# Sheet5.net
KiCad netlist of a schematic drawn in Altium Designer
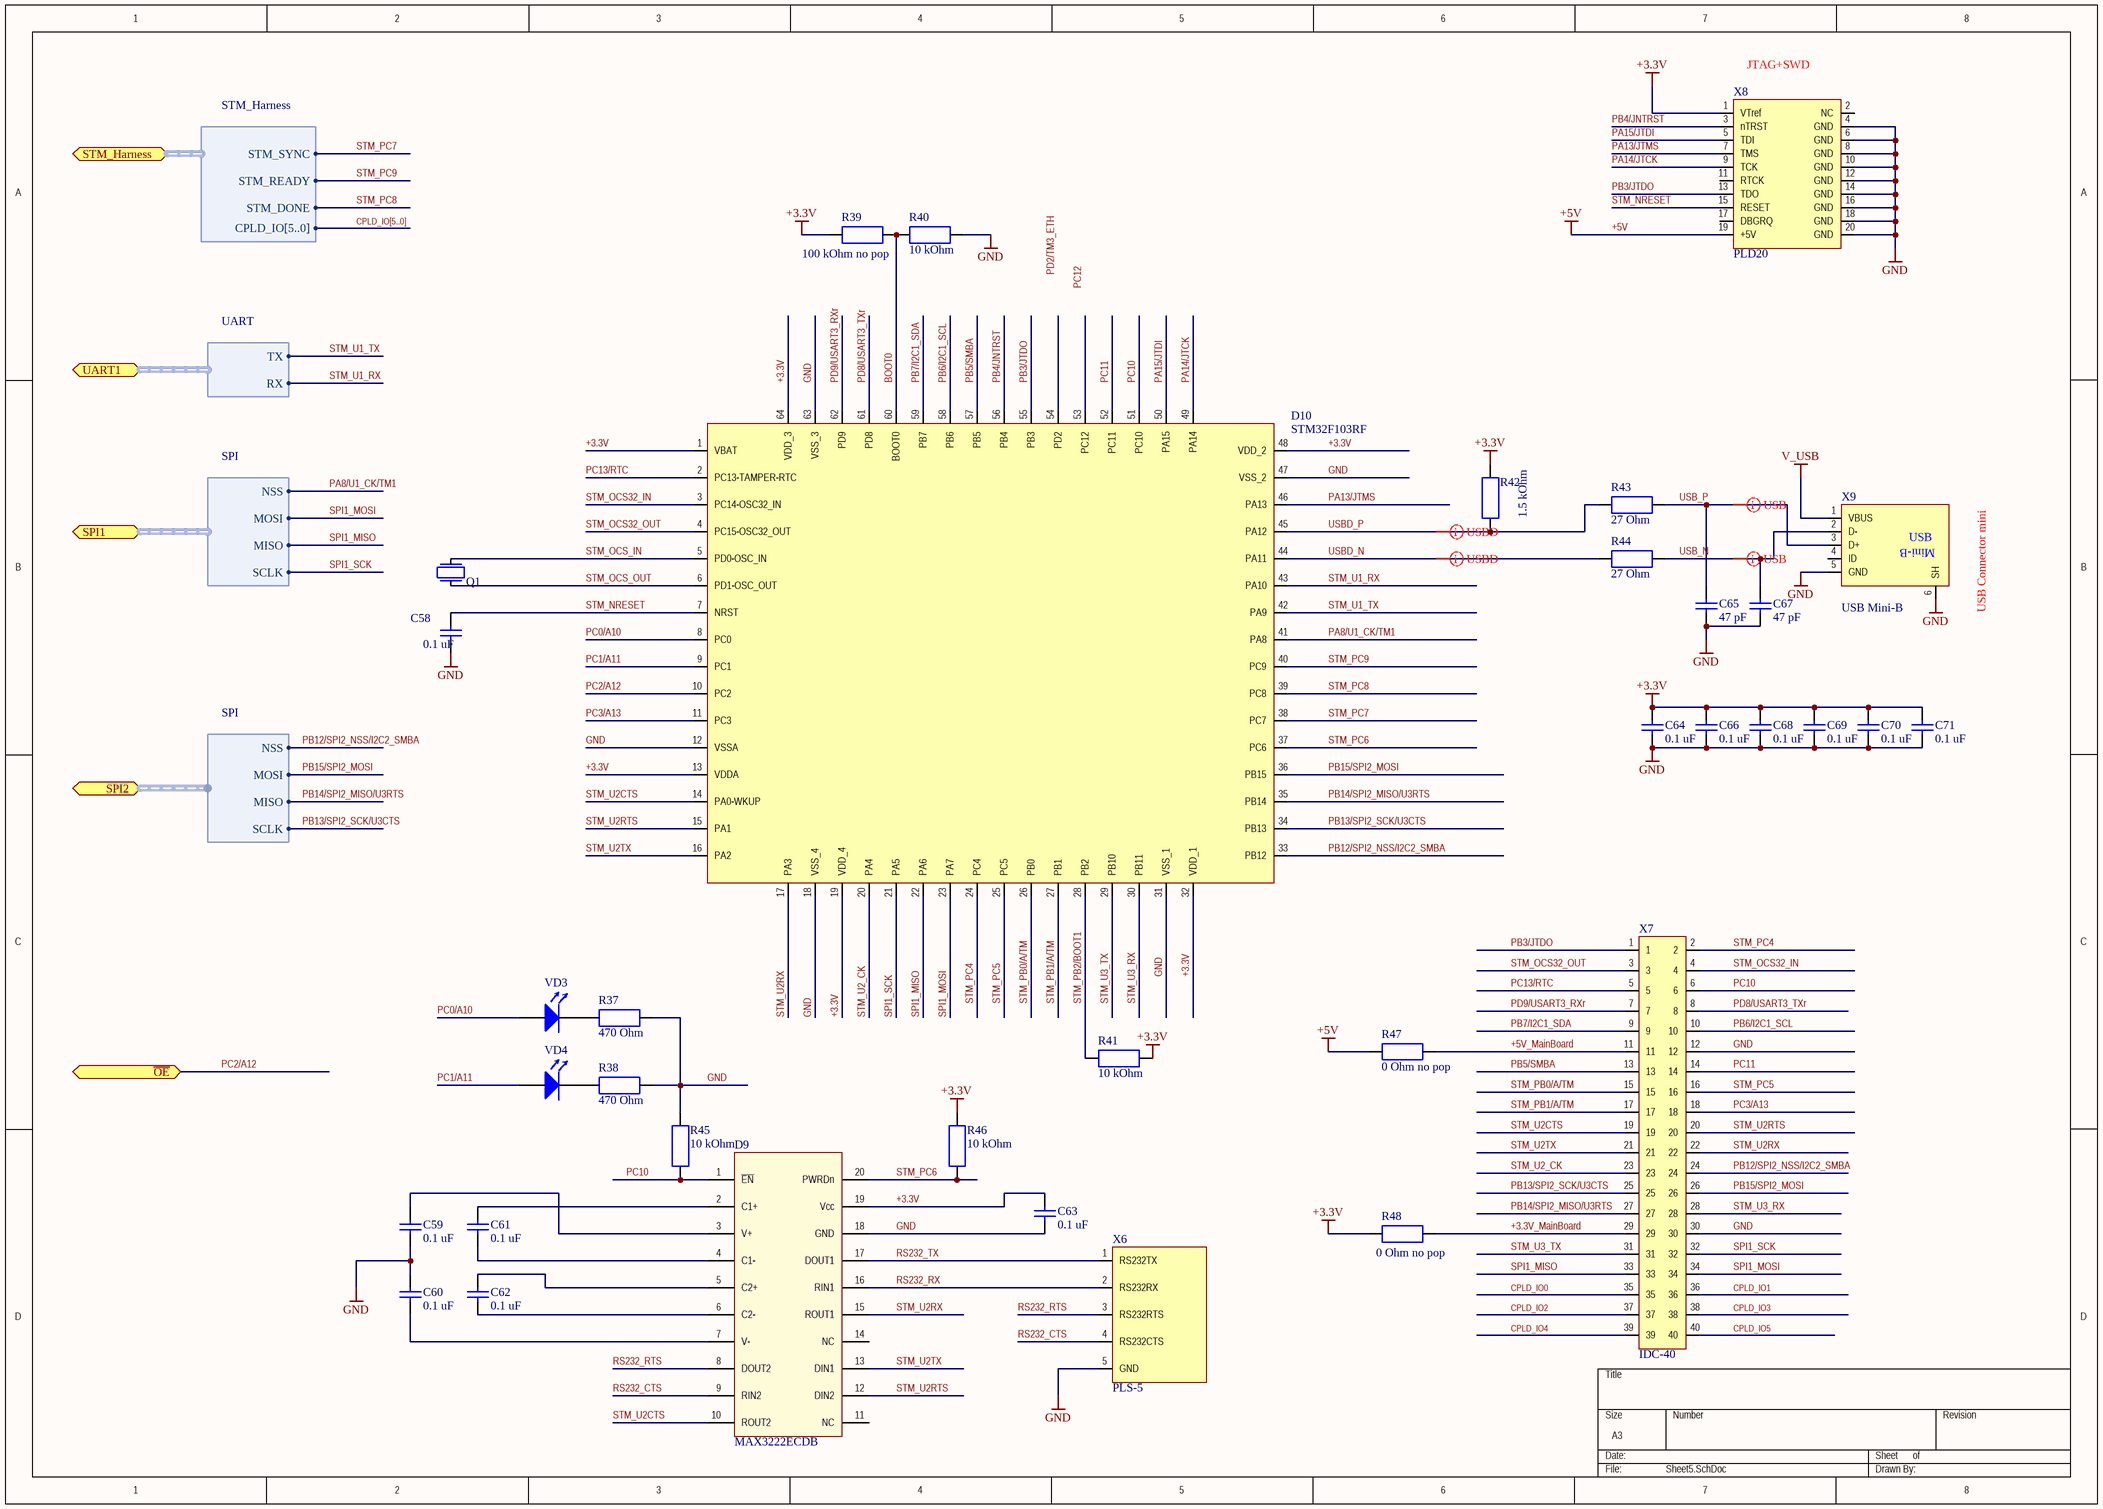
[diagram p0: Sheet5.SchDoc]

(export (version "E")
  (design (tool "Eeschema 10.0.6"))
  (components
    (comp (ref "C58")
      (value "0.1 uF")
      (footprint "CAPC1608N")
      (description "±10%, X7R, 0603")
      (fields (field (name "PUBLISHER") "DS"))
      (libsource (lib "autotracker") (part "CC0603"))
    )
    (comp (ref "C59")
      (value "0.1 uF")
      (footprint "CAPC1608N")
      (description "±10%, X7R, 0603")
      (fields (field (name "PUBLISHER") "DS"))
      (libsource (lib "ADClib") (part "CC0603"))
    )
    (comp (ref "C60")
      (value "0.1 uF")
      (footprint "CAPC1608N")
      (description "±10%, X7R, 0603")
      (fields (field (name "PUBLISHER") "DS"))
      (libsource (lib "ADClib") (part "CC0603"))
    )
    (comp (ref "C61")
      (value "0.1 uF")
      (footprint "CAPC1608N")
      (description "±10%, X7R, 0603")
      (fields (field (name "PUBLISHER") "DS"))
      (libsource (lib "ADClib") (part "CC0603"))
    )
    (comp (ref "C62")
      (value "0.1 uF")
      (footprint "CAPC1608N")
      (description "±10%, X7R, 0603")
      (fields (field (name "PUBLISHER") "DS"))
      (libsource (lib "ADClib") (part "CC0603"))
    )
    (comp (ref "C63")
      (value "0.1 uF")
      (footprint "CAPC1608N")
      (description "±10%, X7R, 0603")
      (fields (field (name "PUBLISHER") "DS"))
      (libsource (lib "ADClib") (part "CC0603"))
    )
    (comp (ref "C64")
      (value "0.1 uF")
      (footprint "CAPC1608N")
      (description "±10%, X7R, 0603")
      (fields (field (name "PUBLISHER") "DS"))
      (libsource (lib "autotracker") (part "CC0603"))
    )
    (comp (ref "C65")
      (value "47 pF")
      (footprint "CAPC1608N")
      (description "±10%, X7R, 0603")
      (fields (field (name "PUBLISHER") "DS"))
      (libsource (lib "autotracker") (part "CC0603"))
    )
    (comp (ref "C66")
      (value "0.1 uF")
      (footprint "CAPC1608N")
      (description "±10%, X7R, 0603")
      (fields (field (name "PUBLISHER") "DS"))
      (libsource (lib "autotracker") (part "CC0603"))
    )
    (comp (ref "C67")
      (value "47 pF")
      (footprint "CAPC1608N")
      (description "±10%, X7R, 0603")
      (fields (field (name "PUBLISHER") "DS"))
      (libsource (lib "autotracker") (part "CC0603"))
    )
    (comp (ref "C68")
      (value "0.1 uF")
      (footprint "CAPC1608N")
      (description "±10%, X7R, 0603")
      (fields (field (name "PUBLISHER") "DS"))
      (libsource (lib "autotracker") (part "CC0603"))
    )
    (comp (ref "C69")
      (value "0.1 uF")
      (footprint "CAPC1608N")
      (description "±10%, X7R, 0603")
      (fields (field (name "PUBLISHER") "DS"))
      (libsource (lib "autotracker") (part "CC0603"))
    )
    (comp (ref "C70")
      (value "0.1 uF")
      (footprint "CAPC1608N")
      (description "±10%, X7R, 0603")
      (fields (field (name "PUBLISHER") "DS"))
      (libsource (lib "autotracker") (part "CC0603"))
    )
    (comp (ref "C71")
      (value "0.1 uF")
      (footprint "CAPC1608N")
      (description "±10%, X7R, 0603")
      (fields (field (name "PUBLISHER") "DS"))
      (libsource (lib "autotracker") (part "CC0603"))
    )
    (comp (ref "D9")
      (value "MAX3222ECDB")
      (footprint "SOP65P780X200-20N")
      (description "RS232 driver")
      (libsource (lib "ADClib") (part "MAX3222ECDB"))
    )
    (comp (ref "D10")
      (value "STM32F103RF")
      (footprint "LQFP64")
      (description "STM32F103RF LQFP64")
      (libsource (lib "ADClib") (part "STM32F103RF"))
    )
    (comp (ref "Q1")
      (value "Quarz")
      (footprint "HC-49/U3H")
      (description "Ceramic quarz")
      (fields (field (name "PUBLISHER") "DS"))
      (libsource (lib "ADClib") (part "Quarz"))
    )
    (comp (ref "R37")
      (value "470 Ohm")
      (footprint "RESC1608N")
      (description "±5%, 0603")
      (fields (field (name "PUBLISHER") "DS"))
      (libsource (lib "ADClib") (part "RES0603"))
    )
    (comp (ref "R38")
      (value "470 Ohm")
      (footprint "RESC1608N")
      (description "±5%, 0603")
      (fields (field (name "PUBLISHER") "DS"))
      (libsource (lib "ADClib") (part "RES0603"))
    )
    (comp (ref "R39")
      (value "100 kOhm no pop")
      (footprint "RESC1608N")
      (description "±5%, 0603")
      (fields (field (name "PUBLISHER") "DS"))
      (libsource (lib "autotracker") (part "RES0603"))
    )
    (comp (ref "R40")
      (value "10 kOhm")
      (footprint "RESC1608N")
      (description "±5%, 0603")
      (fields (field (name "PUBLISHER") "DS"))
      (libsource (lib "autotracker") (part "RES0603"))
    )
    (comp (ref "R41")
      (value "10 kOhm")
      (footprint "RESC1608N")
      (description "±5%, 0603")
      (fields (field (name "PUBLISHER") "DS"))
      (libsource (lib "autotracker") (part "RES0603"))
    )
    (comp (ref "R42")
      (value "1.5 kOhm")
      (footprint "RESC1608N")
      (description "±5%, 0603")
      (fields (field (name "PUBLISHER") "DS"))
      (libsource (lib "autotracker") (part "RES0603"))
    )
    (comp (ref "R43")
      (value "27 Ohm")
      (footprint "RESC1608N")
      (description "±5%, 0603")
      (fields (field (name "PUBLISHER") "DS"))
      (libsource (lib "autotracker") (part "RES0603"))
    )
    (comp (ref "R44")
      (value "27 Ohm")
      (footprint "RESC1608N")
      (description "±5%, 0603")
      (fields (field (name "PUBLISHER") "DS"))
      (libsource (lib "autotracker") (part "RES0603"))
    )
    (comp (ref "R45")
      (value "10 kOhm")
      (footprint "RESC1608N")
      (description "±5%, 0603")
      (fields (field (name "PUBLISHER") "DS"))
      (libsource (lib "ADClib") (part "RES0603"))
    )
    (comp (ref "R46")
      (value "10 kOhm")
      (footprint "RESC1608N")
      (description "±5%, 0603")
      (fields (field (name "PUBLISHER") "DS"))
      (libsource (lib "ADClib") (part "RES0603"))
    )
    (comp (ref "R47")
      (value "0 Ohm no pop")
      (footprint "RESC1608N")
      (description "±5%, 0603")
      (fields (field (name "PUBLISHER") "DS"))
      (libsource (lib "ADClib") (part "RES0603"))
    )
    (comp (ref "R48")
      (value "0 Ohm no pop")
      (footprint "RESC1608N")
      (description "±5%, 0603")
      (fields (field (name "PUBLISHER") "DS"))
      (libsource (lib "ADClib") (part "RES0603"))
    )
    (comp (ref "VD3")
      (value "KP-1608SURC")
      (footprint "LED1608N")
      (fields (field (name "PUBLISHER") "Altium Limited"))
      (libsource (lib "ADClib") (part "KP-1608SURC"))
    )
    (comp (ref "VD4")
      (value "KP-1608SURC")
      (footprint "LED1608N")
      (fields (field (name "PUBLISHER") "Altium Limited"))
      (libsource (lib "ADClib") (part "KP-1608SURC"))
    )
    (comp (ref "X6") (value "PLS-5") (footprint "PLS-5") (libsource (lib "ADClib") (part "RS232")))
    (comp (ref "X7")
      (value "IDC-40")
      (footprint "PLD-40")
      (description "PLD-40 or IDC 40")
      (libsource (lib "ADClib") (part "IDC40"))
    )
    (comp (ref "X8") (value "PLD20") (footprint "PLD-20") (libsource (lib "autotracker") (part "JTAG")))
    (comp (ref "X9")
      (value "USB Mini-B")
      (footprint "USBMINIB")
      (libsource (lib "autotracker") (part "USB-MINI-B"))
    )
  )
  (nets
    (net (code "4") (name "+3.3V") (class "Default")
      (node (ref "C63") (pin "2") (pinfunction "2_2") (pintype "passive"))
      (node (ref "C64") (pin "2") (pinfunction "2_2") (pintype "passive"))
      (node (ref "C66") (pin "2") (pinfunction "2_2") (pintype "passive"))
      (node (ref "C68") (pin "2") (pinfunction "2_2") (pintype "passive"))
      (node (ref "C69") (pin "2") (pinfunction "2_2") (pintype "passive"))
      (node (ref "C70") (pin "2") (pinfunction "2_2") (pintype "passive"))
      (node (ref "C71") (pin "2") (pinfunction "2_2") (pintype "passive"))
      (node (ref "D10") (pin "1") (pinfunction "VBAT_1") (pintype "passive"))
      (node (ref "D10") (pin "13") (pinfunction "VDDA_13") (pintype "passive"))
      (node (ref "D10") (pin "19") (pinfunction "VDD_4_19") (pintype "passive"))
      (node (ref "D10") (pin "32") (pinfunction "VDD_1_32") (pintype "passive"))
      (node (ref "D10") (pin "48") (pinfunction "VDD_2_48") (pintype "passive"))
      (node (ref "D10") (pin "64") (pinfunction "VDD_3_64") (pintype "passive"))
      (node (ref "D9") (pin "19") (pinfunction "Vcc_19") (pintype "passive"))
      (node (ref "R39") (pin "2") (pinfunction "2_2") (pintype "passive"))
      (node (ref "R41") (pin "1") (pinfunction "1_1") (pintype "passive"))
      (node (ref "R42") (pin "2") (pinfunction "2_2") (pintype "passive"))
      (node (ref "R46") (pin "2") (pinfunction "2_2") (pintype "passive"))
      (node (ref "R48") (pin "2") (pinfunction "2_2") (pintype "passive"))
      (node (ref "X8") (pin "1") (pinfunction "VTref_1") (pintype "passive"))
    )
    (net (code "5") (name "+5V") (class "Default")
      (node (ref "R47") (pin "2") (pinfunction "2_2") (pintype "passive"))
      (node (ref "X8") (pin "19") (pinfunction "+5V_19") (pintype "passive"))
    )
    (net (code "6") (name "/+3.3V_MainBoard") (class "Default")
      (node (ref "R48") (pin "1") (pinfunction "1_1") (pintype "passive"))
      (node (ref "X7") (pin "29") (pinfunction "29_29") (pintype "passive"))
    )
    (net (code "7") (name "/+5V_MainBoard") (class "Default")
      (node (ref "R47") (pin "1") (pinfunction "1_1") (pintype "passive"))
      (node (ref "X7") (pin "11") (pinfunction "11_11") (pintype "passive"))
    )
    (net (code "8") (name "/BOOT0") (class "Default")
      (node (ref "D10") (pin "60") (pinfunction "BOOT0_60") (pintype "passive"))
      (node (ref "R39") (pin "1") (pinfunction "1_1") (pintype "passive"))
      (node (ref "R40") (pin "2") (pinfunction "2_2") (pintype "passive"))
    )
    (net (code "9") (name "/CPLD_IO0") (class "Default")
      (node (ref "X7") (pin "35") (pinfunction "35_35") (pintype "passive"))
    )
    (net (code "10") (name "/CPLD_IO1") (class "Default")
      (node (ref "X7") (pin "36") (pinfunction "36_36") (pintype "passive"))
    )
    (net (code "11") (name "/CPLD_IO2") (class "Default")
      (node (ref "X7") (pin "37") (pinfunction "37_37") (pintype "passive"))
    )
    (net (code "12") (name "/CPLD_IO3") (class "Default")
      (node (ref "X7") (pin "38") (pinfunction "38_38") (pintype "passive"))
    )
    (net (code "13") (name "/CPLD_IO4") (class "Default")
      (node (ref "X7") (pin "39") (pinfunction "39_39") (pintype "passive"))
    )
    (net (code "14") (name "/CPLD_IO5") (class "Default")
      (node (ref "X7") (pin "40") (pinfunction "40_40") (pintype "passive"))
    )
    (net (code "15") (name "/PA8{slash}U1_CK{slash}TM1") (class "Default")
      (node (ref "D10") (pin "41") (pinfunction "PA8_41") (pintype "passive"))
    )
    (net (code "16") (name "/PA13{slash}JTMS") (class "Default")
      (node (ref "D10") (pin "46") (pinfunction "PA13_46") (pintype "passive"))
      (node (ref "X8") (pin "7") (pinfunction "TMS_7") (pintype "passive"))
    )
    (net (code "17") (name "/PA14{slash}JTCK") (class "Default")
      (node (ref "D10") (pin "49") (pinfunction "PA14_49") (pintype "passive"))
      (node (ref "X8") (pin "9") (pinfunction "TCK_9") (pintype "passive"))
    )
    (net (code "18") (name "/PA15{slash}JTDI") (class "Default")
      (node (ref "D10") (pin "50") (pinfunction "PA15_50") (pintype "passive"))
      (node (ref "X8") (pin "5") (pinfunction "TDI_5") (pintype "passive"))
    )
    (net (code "19") (name "/PB3{slash}JTDO") (class "Default")
      (node (ref "D10") (pin "55") (pinfunction "PB3_55") (pintype "passive"))
      (node (ref "X7") (pin "1") (pinfunction "1_1") (pintype "passive"))
      (node (ref "X8") (pin "13") (pinfunction "TDO_13") (pintype "passive"))
    )
    (net (code "20") (name "/PB4{slash}JNTRST") (class "Default")
      (node (ref "D10") (pin "56") (pinfunction "PB4_56") (pintype "passive"))
      (node (ref "X8") (pin "3") (pinfunction "nTRST_3") (pintype "passive"))
    )
    (net (code "21") (name "/PB5{slash}SMBA") (class "Default")
      (node (ref "D10") (pin "57") (pinfunction "PB5_57") (pintype "passive"))
      (node (ref "X7") (pin "13") (pinfunction "13_13") (pintype "passive"))
    )
    (net (code "22") (name "/PB6{slash}I2C1_SCL") (class "Default")
      (node (ref "D10") (pin "58") (pinfunction "PB6_58") (pintype "passive"))
      (node (ref "X7") (pin "10") (pinfunction "10_10") (pintype "passive"))
    )
    (net (code "23") (name "/PB7{slash}I2C1_SDA") (class "Default")
      (node (ref "D10") (pin "59") (pinfunction "PB7_59") (pintype "passive"))
      (node (ref "X7") (pin "9") (pinfunction "9_9") (pintype "passive"))
    )
    (net (code "24") (name "/PB12{slash}SPI2_NSS{slash}I2C2_SMBA") (class "Default")
      (node (ref "D10") (pin "33") (pinfunction "PB12_33") (pintype "passive"))
      (node (ref "X7") (pin "24") (pinfunction "24_24") (pintype "passive"))
    )
    (net (code "25") (name "/PB13{slash}SPI2_SCK{slash}U3CTS") (class "Default")
      (node (ref "D10") (pin "34") (pinfunction "PB13_34") (pintype "passive"))
      (node (ref "X7") (pin "25") (pinfunction "25_25") (pintype "passive"))
    )
    (net (code "26") (name "/PB14{slash}SPI2_MISO{slash}U3RTS") (class "Default")
      (node (ref "D10") (pin "35") (pinfunction "PB14_35") (pintype "passive"))
      (node (ref "X7") (pin "27") (pinfunction "27_27") (pintype "passive"))
    )
    (net (code "27") (name "/PB15{slash}SPI2_MOSI") (class "Default")
      (node (ref "D10") (pin "36") (pinfunction "PB15_36") (pintype "passive"))
      (node (ref "X7") (pin "26") (pinfunction "26_26") (pintype "passive"))
    )
    (net (code "28") (name "/PC0{slash}A10") (class "Default")
      (node (ref "D10") (pin "8") (pinfunction "PC0_8") (pintype "passive"))
      (node (ref "VD3") (pin "1") (pinfunction "A_1") (pintype "passive"))
    )
    (net (code "29") (name "/PC1{slash}A11") (class "Default")
      (node (ref "D10") (pin "9") (pinfunction "PC1_9") (pintype "passive"))
      (node (ref "VD4") (pin "1") (pinfunction "A_1") (pintype "passive"))
    )
    (net (code "30") (name "/PC2{slash}A12") (class "Default")
      (node (ref "D10") (pin "10") (pinfunction "PC2_10") (pintype "passive"))
    )
    (net (code "31") (name "/PC3{slash}A13") (class "Default")
      (node (ref "D10") (pin "11") (pinfunction "PC3_11") (pintype "passive"))
      (node (ref "X7") (pin "18") (pinfunction "18_18") (pintype "passive"))
    )
    (net (code "32") (name "/PC10") (class "Default")
      (node (ref "D10") (pin "51") (pinfunction "PC10_51") (pintype "passive"))
      (node (ref "D9") (pin "1") (pinfunction "~{EN}_1") (pintype "passive"))
      (node (ref "R45") (pin "1") (pinfunction "1_1") (pintype "passive"))
      (node (ref "X7") (pin "6") (pinfunction "6_6") (pintype "passive"))
    )
    (net (code "33") (name "/PC11") (class "Default")
      (node (ref "D10") (pin "52") (pinfunction "PC11_52") (pintype "passive"))
      (node (ref "X7") (pin "14") (pinfunction "14_14") (pintype "passive"))
    )
    (net (code "35") (name "/PC13{slash}RTC") (class "Default")
      (node (ref "D10") (pin "2") (pinfunction "PC13-TAMPER-RTC_2") (pintype "passive"))
      (node (ref "X7") (pin "5") (pinfunction "5_5") (pintype "passive"))
    )
    (net (code "37") (name "/PD8{slash}USART3_TXr") (class "Default")
      (node (ref "D10") (pin "61") (pinfunction "PD8_61") (pintype "passive"))
      (node (ref "X7") (pin "8") (pinfunction "8_8") (pintype "passive"))
    )
    (net (code "38") (name "/PD9{slash}USART3_RXr") (class "Default")
      (node (ref "D10") (pin "62") (pinfunction "PD9_62") (pintype "passive"))
      (node (ref "X7") (pin "7") (pinfunction "7_7") (pintype "passive"))
    )
    (net (code "39") (name "/RS232_CTS") (class "Default")
      (node (ref "D9") (pin "9") (pinfunction "RIN2_9") (pintype "passive"))
      (node (ref "X6") (pin "4") (pinfunction "RS232CTS_4") (pintype "passive"))
    )
    (net (code "40") (name "/RS232_RTS") (class "Default")
      (node (ref "D9") (pin "8") (pinfunction "DOUT2_8") (pintype "passive"))
      (node (ref "X6") (pin "3") (pinfunction "RS232RTS_3") (pintype "passive"))
    )
    (net (code "41") (name "/RS232_RX") (class "Default")
      (node (ref "D9") (pin "16") (pinfunction "RIN1_16") (pintype "passive"))
      (node (ref "X6") (pin "2") (pinfunction "RS232RX_2") (pintype "passive"))
    )
    (net (code "42") (name "/RS232_TX") (class "Default")
      (node (ref "D9") (pin "17") (pinfunction "DOUT1_17") (pintype "passive"))
      (node (ref "X6") (pin "1") (pinfunction "RS232TX_1") (pintype "passive"))
    )
    (net (code "43") (name "/SPI1_MISO") (class "Default")
      (node (ref "D10") (pin "22") (pinfunction "PA6_22") (pintype "passive"))
      (node (ref "X7") (pin "33") (pinfunction "33_33") (pintype "passive"))
    )
    (net (code "44") (name "/SPI1_MOSI") (class "Default")
      (node (ref "D10") (pin "23") (pinfunction "PA7_23") (pintype "passive"))
      (node (ref "X7") (pin "34") (pinfunction "34_34") (pintype "passive"))
    )
    (net (code "45") (name "/SPI1_SCK") (class "Default")
      (node (ref "D10") (pin "21") (pinfunction "PA5_21") (pintype "passive"))
      (node (ref "X7") (pin "32") (pinfunction "32_32") (pintype "passive"))
    )
    (net (code "47") (name "/STM_NRESET") (class "Default")
      (node (ref "C58") (pin "2") (pinfunction "2_2") (pintype "passive"))
      (node (ref "D10") (pin "7") (pinfunction "NRST_7") (pintype "passive"))
      (node (ref "X8") (pin "15") (pinfunction "RESET_15") (pintype "passive"))
    )
    (net (code "48") (name "/STM_OCS32_IN") (class "Default")
      (node (ref "D10") (pin "3") (pinfunction "PC14-OSC32_IN_3") (pintype "passive"))
      (node (ref "X7") (pin "4") (pinfunction "4_4") (pintype "passive"))
    )
    (net (code "49") (name "/STM_OCS32_OUT") (class "Default")
      (node (ref "D10") (pin "4") (pinfunction "PC15-OSC32_OUT_4") (pintype "passive"))
      (node (ref "X7") (pin "3") (pinfunction "3_3") (pintype "passive"))
    )
    (net (code "50") (name "/STM_OCS_IN") (class "Default")
      (node (ref "D10") (pin "5") (pinfunction "PD0-OSC_IN_5") (pintype "passive"))
      (node (ref "Q1") (pin "2") (pinfunction "2_2") (pintype "passive"))
    )
    (net (code "51") (name "/STM_OCS_OUT") (class "Default")
      (node (ref "D10") (pin "6") (pinfunction "PD1-OSC_OUT_6") (pintype "passive"))
      (node (ref "Q1") (pin "1") (pinfunction "1_1") (pintype "passive"))
    )
    (net (code "52") (name "/STM_PB0{slash}A{slash}TM") (class "Default")
      (node (ref "D10") (pin "26") (pinfunction "PB0_26") (pintype "passive"))
      (node (ref "X7") (pin "15") (pinfunction "15_15") (pintype "passive"))
    )
    (net (code "53") (name "/STM_PB1{slash}A{slash}TM") (class "Default")
      (node (ref "D10") (pin "27") (pinfunction "PB1_27") (pintype "passive"))
      (node (ref "X7") (pin "17") (pinfunction "17_17") (pintype "passive"))
    )
    (net (code "54") (name "/STM_PB2{slash}BOOT1") (class "Default")
      (node (ref "D10") (pin "28") (pinfunction "PB2_28") (pintype "passive"))
      (node (ref "R41") (pin "2") (pinfunction "2_2") (pintype "passive"))
    )
    (net (code "55") (name "/STM_PC4") (class "Default")
      (node (ref "D10") (pin "24") (pinfunction "PC4_24") (pintype "passive"))
      (node (ref "X7") (pin "2") (pinfunction "2_2") (pintype "passive"))
    )
    (net (code "56") (name "/STM_PC5") (class "Default")
      (node (ref "D10") (pin "25") (pinfunction "PC5_25") (pintype "passive"))
      (node (ref "X7") (pin "16") (pinfunction "16_16") (pintype "passive"))
    )
    (net (code "57") (name "/STM_PC6") (class "Default")
      (node (ref "D10") (pin "37") (pinfunction "PC6_37") (pintype "passive"))
      (node (ref "D9") (pin "20") (pinfunction "PWRDn_20") (pintype "passive"))
      (node (ref "R46") (pin "1") (pinfunction "1_1") (pintype "passive"))
    )
    (net (code "58") (name "/STM_PC7") (class "Default")
      (node (ref "D10") (pin "38") (pinfunction "PC7_38") (pintype "passive"))
    )
    (net (code "59") (name "/STM_PC8") (class "Default")
      (node (ref "D10") (pin "39") (pinfunction "PC8_39") (pintype "passive"))
    )
    (net (code "60") (name "/STM_PC9") (class "Default")
      (node (ref "D10") (pin "40") (pinfunction "PC9_40") (pintype "passive"))
    )
    (net (code "61") (name "/STM_U1_RX") (class "Default")
      (node (ref "D10") (pin "43") (pinfunction "PA10_43") (pintype "passive"))
    )
    (net (code "62") (name "/STM_U1_TX") (class "Default")
      (node (ref "D10") (pin "42") (pinfunction "PA9_42") (pintype "passive"))
    )
    (net (code "63") (name "/STM_U2CTS") (class "Default")
      (node (ref "D10") (pin "14") (pinfunction "PA0-WKUP_14") (pintype "passive"))
      (node (ref "D9") (pin "10") (pinfunction "ROUT2_10") (pintype "passive"))
      (node (ref "X7") (pin "19") (pinfunction "19_19") (pintype "passive"))
    )
    (net (code "64") (name "/STM_U2RTS") (class "Default")
      (node (ref "D10") (pin "15") (pinfunction "PA1_15") (pintype "passive"))
      (node (ref "D9") (pin "12") (pinfunction "DIN2_12") (pintype "passive"))
      (node (ref "X7") (pin "20") (pinfunction "20_20") (pintype "passive"))
    )
    (net (code "65") (name "/STM_U2RX") (class "Default")
      (node (ref "D10") (pin "17") (pinfunction "PA3_17") (pintype "passive"))
      (node (ref "D9") (pin "15") (pinfunction "ROUT1_15") (pintype "passive"))
      (node (ref "X7") (pin "22") (pinfunction "22_22") (pintype "passive"))
    )
    (net (code "66") (name "/STM_U2TX") (class "Default")
      (node (ref "D10") (pin "16") (pinfunction "PA2_16") (pintype "passive"))
      (node (ref "D9") (pin "13") (pinfunction "DIN1_13") (pintype "passive"))
      (node (ref "X7") (pin "21") (pinfunction "21_21") (pintype "passive"))
    )
    (net (code "67") (name "/STM_U2_CK") (class "Default")
      (node (ref "D10") (pin "20") (pinfunction "PA4_20") (pintype "passive"))
      (node (ref "X7") (pin "23") (pinfunction "23_23") (pintype "passive"))
    )
    (net (code "68") (name "/STM_U3_RX") (class "Default")
      (node (ref "D10") (pin "30") (pinfunction "PB11_30") (pintype "passive"))
      (node (ref "X7") (pin "28") (pinfunction "28_28") (pintype "passive"))
    )
    (net (code "69") (name "/STM_U3_TX") (class "Default")
      (node (ref "D10") (pin "29") (pinfunction "PB10_29") (pintype "passive"))
      (node (ref "X7") (pin "31") (pinfunction "31_31") (pintype "passive"))
    )
    (net (code "70") (name "/USBD_N") (class "Default")
      (node (ref "D10") (pin "44") (pinfunction "PA11_44") (pintype "passive"))
      (node (ref "R44") (pin "2") (pinfunction "2_2") (pintype "passive"))
    )
    (net (code "71") (name "/USBD_P") (class "Default")
      (node (ref "D10") (pin "45") (pinfunction "PA12_45") (pintype "passive"))
      (node (ref "R42") (pin "1") (pinfunction "1_1") (pintype "passive"))
      (node (ref "R43") (pin "2") (pinfunction "2_2") (pintype "passive"))
    )
    (net (code "72") (name "/USB_N") (class "Default")
      (node (ref "C67") (pin "2") (pinfunction "2_2") (pintype "passive"))
      (node (ref "R44") (pin "1") (pinfunction "1_1") (pintype "passive"))
      (node (ref "X9") (pin "2") (pinfunction "D-_2") (pintype "passive"))
    )
    (net (code "73") (name "/USB_P") (class "Default")
      (node (ref "C65") (pin "2") (pinfunction "2_2") (pintype "passive"))
      (node (ref "R43") (pin "1") (pinfunction "1_1") (pintype "passive"))
      (node (ref "X9") (pin "3") (pinfunction "D+_3") (pintype "passive"))
    )
    (net (code "77") (name "GND") (class "Default")
      (node (ref "C58") (pin "1") (pinfunction "1_1") (pintype "passive"))
      (node (ref "C59") (pin "1") (pinfunction "1_1") (pintype "passive"))
      (node (ref "C60") (pin "2") (pinfunction "2_2") (pintype "passive"))
      (node (ref "C63") (pin "1") (pinfunction "1_1") (pintype "passive"))
      (node (ref "C64") (pin "1") (pinfunction "1_1") (pintype "passive"))
      (node (ref "C65") (pin "1") (pinfunction "1_1") (pintype "passive"))
      (node (ref "C66") (pin "1") (pinfunction "1_1") (pintype "passive"))
      (node (ref "C67") (pin "1") (pinfunction "1_1") (pintype "passive"))
      (node (ref "C68") (pin "1") (pinfunction "1_1") (pintype "passive"))
      (node (ref "C69") (pin "1") (pinfunction "1_1") (pintype "passive"))
      (node (ref "C70") (pin "1") (pinfunction "1_1") (pintype "passive"))
      (node (ref "C71") (pin "1") (pinfunction "1_1") (pintype "passive"))
      (node (ref "D10") (pin "12") (pinfunction "VSSA_12") (pintype "passive"))
      (node (ref "D10") (pin "18") (pinfunction "VSS_4_18") (pintype "passive"))
      (node (ref "D10") (pin "31") (pinfunction "VSS_1_31") (pintype "passive"))
      (node (ref "D10") (pin "47") (pinfunction "VSS_2_47") (pintype "passive"))
      (node (ref "D10") (pin "63") (pinfunction "VSS_3_63") (pintype "passive"))
      (node (ref "D9") (pin "18") (pinfunction "GND_18") (pintype "passive"))
      (node (ref "R37") (pin "2") (pinfunction "2_2") (pintype "passive"))
      (node (ref "R38") (pin "2") (pinfunction "2_2") (pintype "passive"))
      (node (ref "R40") (pin "1") (pinfunction "1_1") (pintype "passive"))
      (node (ref "R45") (pin "2") (pinfunction "2_2") (pintype "passive"))
      (node (ref "X6") (pin "5") (pinfunction "GND_5") (pintype "passive"))
      (node (ref "X7") (pin "12") (pinfunction "12_12") (pintype "passive"))
      (node (ref "X7") (pin "30") (pinfunction "30_30") (pintype "passive"))
      (node (ref "X8") (pin "10") (pinfunction "GND_10") (pintype "passive"))
      (node (ref "X8") (pin "12") (pinfunction "GND_12") (pintype "passive"))
      (node (ref "X8") (pin "14") (pinfunction "GND_14") (pintype "passive"))
      (node (ref "X8") (pin "16") (pinfunction "GND_16") (pintype "passive"))
      (node (ref "X8") (pin "18") (pinfunction "GND_18") (pintype "passive"))
      (node (ref "X8") (pin "20") (pinfunction "GND_20") (pintype "passive"))
      (node (ref "X8") (pin "4") (pinfunction "GND_4") (pintype "passive"))
      (node (ref "X8") (pin "6") (pinfunction "GND_6") (pintype "passive"))
      (node (ref "X8") (pin "8") (pinfunction "GND_8") (pintype "passive"))
      (node (ref "X9") (pin "5") (pinfunction "GND_5") (pintype "passive"))
      (node (ref "X9") (pin "6") (pinfunction "SH_6") (pintype "passive"))
    )
    (net (code "78") (name "Net-(D9-C1+)") (class "Default")
      (node (ref "C61") (pin "2") (pinfunction "2_2") (pintype "passive"))
      (node (ref "D9") (pin "2") (pinfunction "C1+_2") (pintype "passive"))
    )
    (net (code "79") (name "Net-(D9-C1-)") (class "Default")
      (node (ref "C61") (pin "1") (pinfunction "1_1") (pintype "passive"))
      (node (ref "D9") (pin "4") (pinfunction "C1-_4") (pintype "passive"))
    )
    (net (code "80") (name "Net-(D9-C2+)") (class "Default")
      (node (ref "C62") (pin "2") (pinfunction "2_2") (pintype "passive"))
      (node (ref "D9") (pin "5") (pinfunction "C2+_5") (pintype "passive"))
    )
    (net (code "81") (name "Net-(D9-C2-)") (class "Default")
      (node (ref "C62") (pin "1") (pinfunction "1_1") (pintype "passive"))
      (node (ref "D9") (pin "6") (pinfunction "C2-_6") (pintype "passive"))
    )
    (net (code "82") (name "Net-(D9-V+)") (class "Default")
      (node (ref "C59") (pin "2") (pinfunction "2_2") (pintype "passive"))
      (node (ref "D9") (pin "3") (pinfunction "V+_3") (pintype "passive"))
    )
    (net (code "83") (name "Net-(D9-V-)") (class "Default")
      (node (ref "C60") (pin "1") (pinfunction "1_1") (pintype "passive"))
      (node (ref "D9") (pin "7") (pinfunction "V-_7") (pintype "passive"))
    )
    (net (code "84") (name "Net-(VD3-K)") (class "Default")
      (node (ref "R37") (pin "1") (pinfunction "1_1") (pintype "passive"))
      (node (ref "VD3") (pin "2") (pinfunction "K_2") (pintype "passive"))
    )
    (net (code "85") (name "Net-(VD4-K)") (class "Default")
      (node (ref "R38") (pin "1") (pinfunction "1_1") (pintype "passive"))
      (node (ref "VD4") (pin "2") (pinfunction "K_2") (pintype "passive"))
    )
    (net (code "86") (name "V_USB") (class "Default")
      (node (ref "X9") (pin "1") (pinfunction "VBUS_1") (pintype "passive"))
    )
    (net (code "87") (name "unconnected-(D9-NC-Pad11)") (class "Default")
      (node (ref "D9") (pin "11") (pinfunction "NC_11") (pintype "passive"))
    )
    (net (code "88") (name "unconnected-(D9-NC-Pad14)") (class "Default")
      (node (ref "D9") (pin "14") (pinfunction "NC_14") (pintype "passive"))
    )
    (net (code "89") (name "unconnected-(D10-PC12-Pad53)") (class "Default")
      (node (ref "D10") (pin "53") (pinfunction "PC12_53") (pintype "passive"))
    )
    (net (code "90") (name "unconnected-(D10-PD2-Pad54)") (class "Default")
      (node (ref "D10") (pin "54") (pinfunction "PD2_54") (pintype "passive"))
    )
    (net (code "91") (name "unconnected-(X8-DBGRQ-Pad17)") (class "Default")
      (node (ref "X8") (pin "17") (pinfunction "DBGRQ_17") (pintype "passive"))
    )
    (net (code "92") (name "unconnected-(X8-NC-Pad2)") (class "Default")
      (node (ref "X8") (pin "2") (pinfunction "NC_2") (pintype "passive"))
    )
    (net (code "93") (name "unconnected-(X8-RTCK-Pad11)") (class "Default")
      (node (ref "X8") (pin "11") (pinfunction "RTCK_11") (pintype "passive"))
    )
    (net (code "94") (name "unconnected-(X9-ID-Pad4)") (class "Default")
      (node (ref "X9") (pin "4") (pinfunction "ID_4") (pintype "passive"))
    )
  )
)
